# Ethernet_Connector.net
KiCad netlist of a schematic drawn in Altium Designer
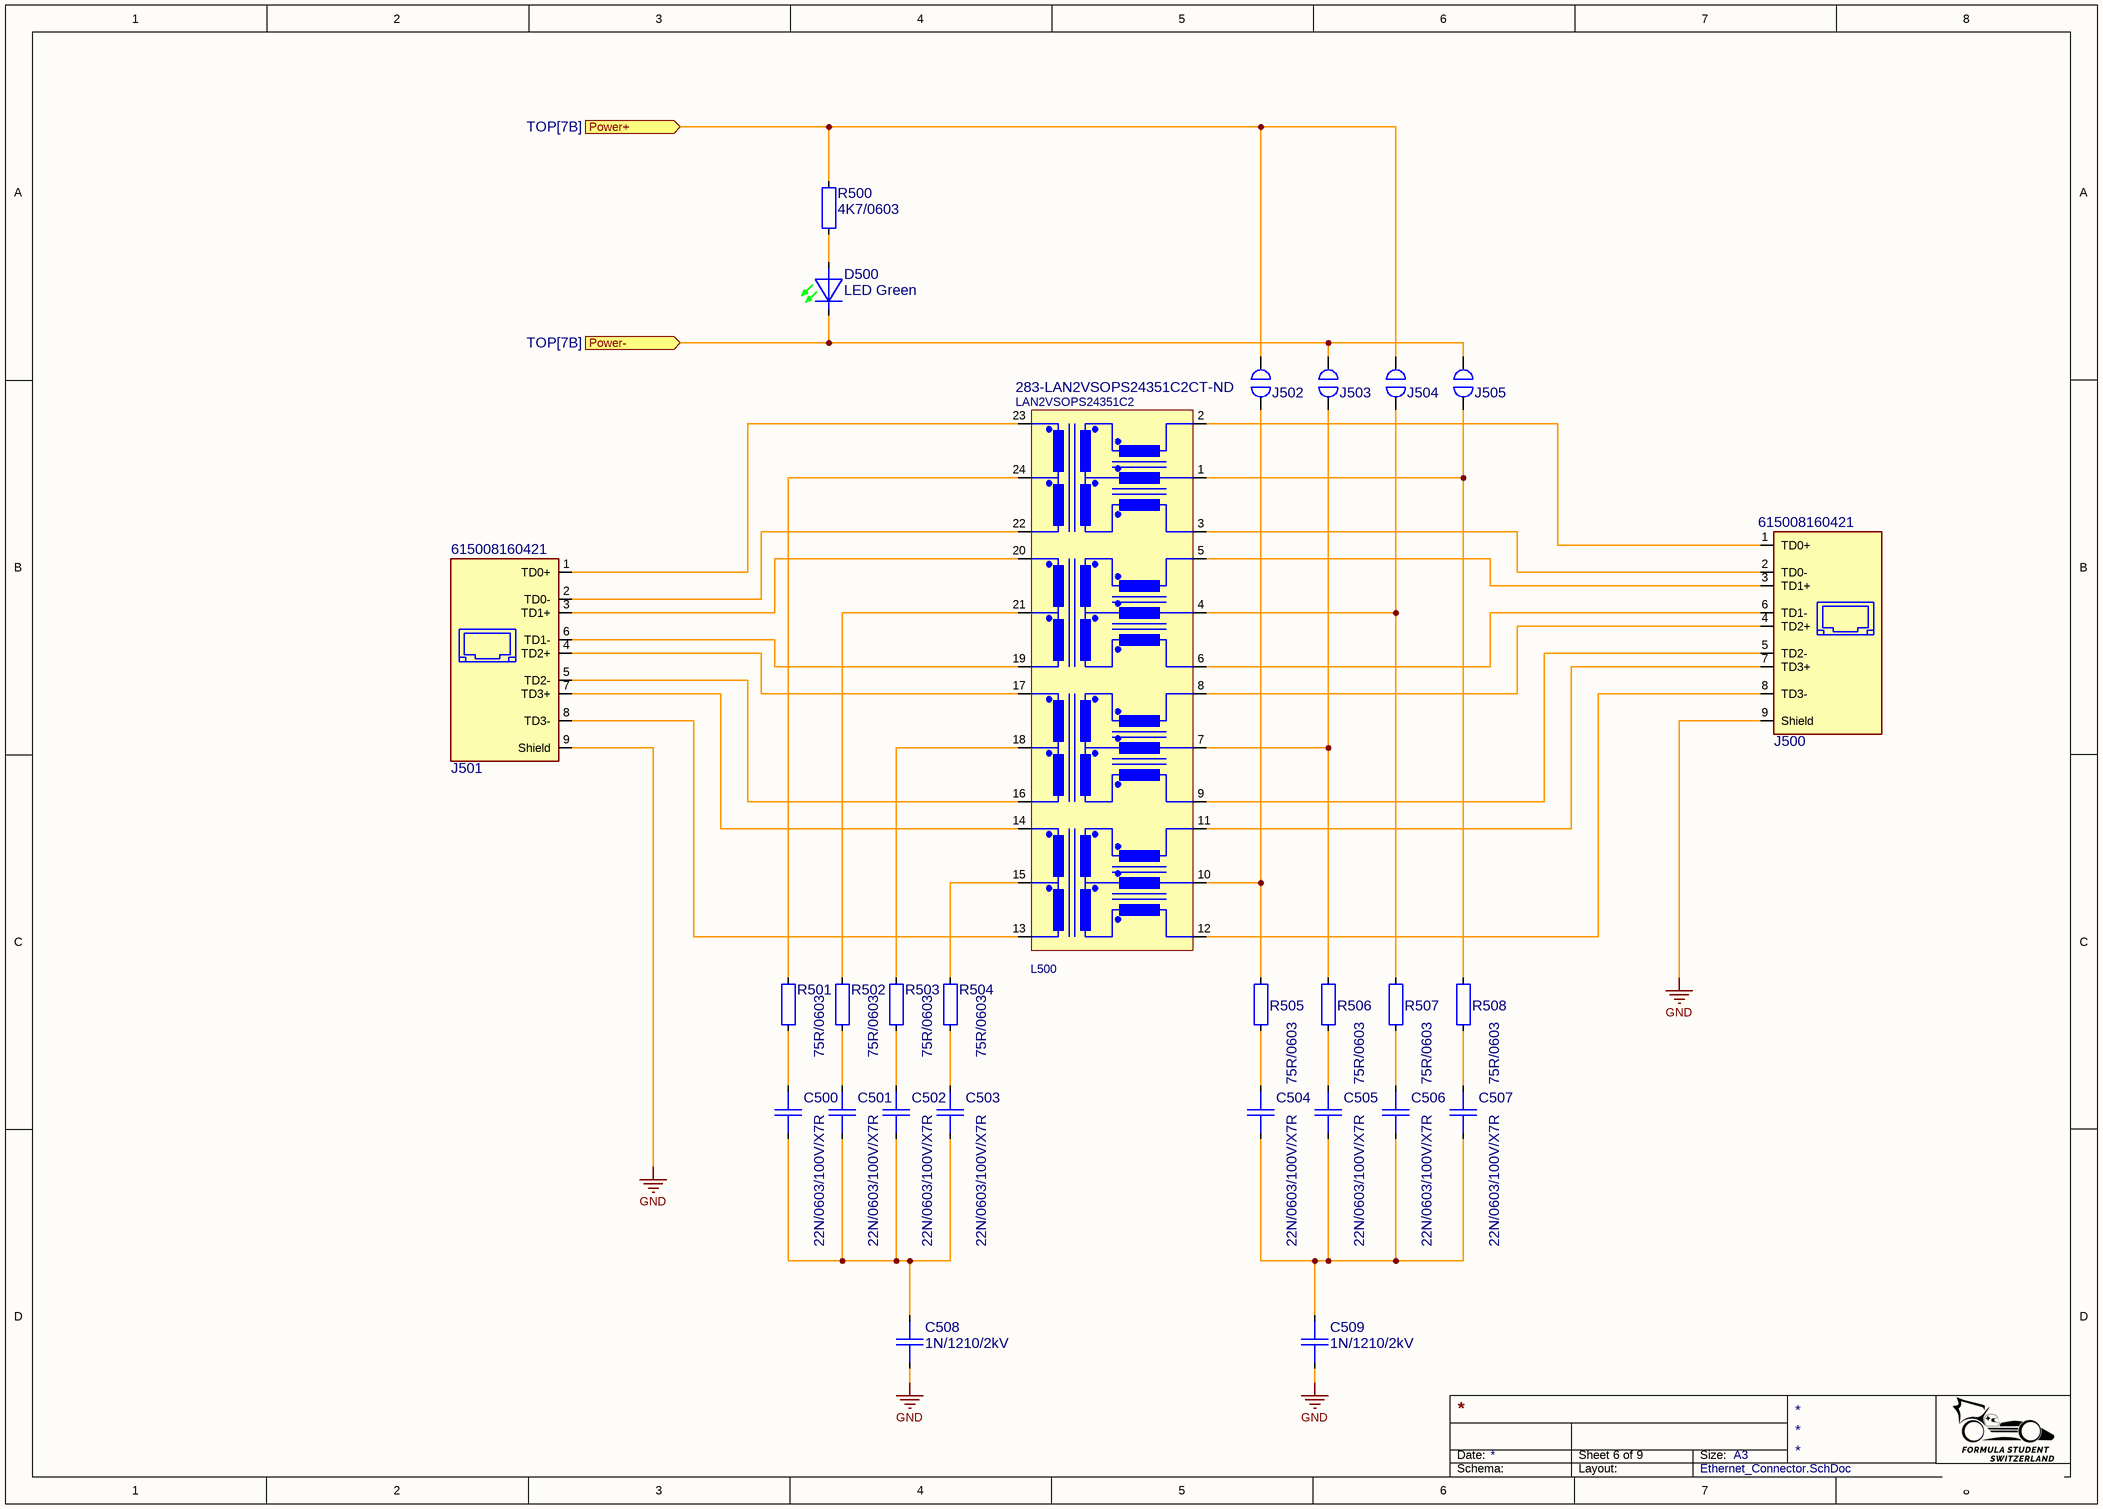
[diagram p0: Ethernet_Connector.SchDoc]

(export (version "E")
  (design (tool "Eeschema 10.0.6"))
  (components
    (comp (ref "C500")
      (value "22N/0603/100V/X7R")
      (footprint "CAP0603_X7R")
      (description "CAP SM 0603 22nF 100V X7R")
      (fields (field (name "MANUFACTURER") "GENERIC"))
      (libsource (lib "daniw_altium_lib") (part "C"))
    )
    (comp (ref "C501")
      (value "22N/0603/100V/X7R")
      (footprint "CAP0603_X7R")
      (description "CAP SM 0603 22nF 100V X7R")
      (fields (field (name "MANUFACTURER") "GENERIC"))
      (libsource (lib "daniw_altium_lib") (part "C"))
    )
    (comp (ref "C502")
      (value "22N/0603/100V/X7R")
      (footprint "CAP0603_X7R")
      (description "CAP SM 0603 22nF 100V X7R")
      (fields (field (name "MANUFACTURER") "GENERIC"))
      (libsource (lib "daniw_altium_lib") (part "C"))
    )
    (comp (ref "C503")
      (value "22N/0603/100V/X7R")
      (footprint "CAP0603_X7R")
      (description "CAP SM 0603 22nF 100V X7R")
      (fields (field (name "MANUFACTURER") "GENERIC"))
      (libsource (lib "daniw_altium_lib") (part "C"))
    )
    (comp (ref "C504")
      (value "22N/0603/100V/X7R")
      (footprint "CAP0603_X7R")
      (description "CAP SM 0603 22nF 100V X7R")
      (fields (field (name "MANUFACTURER") "GENERIC"))
      (libsource (lib "daniw_altium_lib") (part "C"))
    )
    (comp (ref "C505")
      (value "22N/0603/100V/X7R")
      (footprint "CAP0603_X7R")
      (description "CAP SM 0603 22nF 100V X7R")
      (fields (field (name "MANUFACTURER") "GENERIC"))
      (libsource (lib "daniw_altium_lib") (part "C"))
    )
    (comp (ref "C506")
      (value "22N/0603/100V/X7R")
      (footprint "CAP0603_X7R")
      (description "CAP SM 0603 22nF 100V X7R")
      (fields (field (name "MANUFACTURER") "GENERIC"))
      (libsource (lib "daniw_altium_lib") (part "C"))
    )
    (comp (ref "C507")
      (value "22N/0603/100V/X7R")
      (footprint "CAP0603_X7R")
      (description "CAP SM 0603 22nF 100V X7R")
      (fields (field (name "MANUFACTURER") "GENERIC"))
      (libsource (lib "daniw_altium_lib") (part "C"))
    )
    (comp (ref "C508")
      (value "1N/1210/2kV")
      (footprint "CAP1210_X7R")
      (description "CAP SM 1210 1nF 2kV")
      (fields (field (name "MANUFACTURER") "GENERIC"))
      (libsource (lib "daniw_altium_lib") (part "C"))
    )
    (comp (ref "C509")
      (value "1N/1210/2kV")
      (footprint "CAP1210_X7R")
      (description "CAP SM 1210 1nF 2kV")
      (fields (field (name "MANUFACTURER") "GENERIC"))
      (libsource (lib "daniw_altium_lib") (part "C"))
    )
    (comp (ref "D500")
      (value "LED Green")
      (footprint "LED0603_GREEN")
      (description "Generic LED Green 0603")
      (fields (field (name "PART NUMBER") "LED Green 0603") (field (name "MANUFACTURER") "GENERIC"))
      (libsource (lib "daniw_altium_lib") (part "LED_GREEN"))
    )
    (comp (ref "J500")
      (value "615008160421")
      (footprint "ETH_615008160421")
      (description "CONN MOD JACK 8P8C VERT SHIELDED")
      (fields (field (name "PART NUMBER") "ETH_THT_Vert_Schielded") (field (name "MANUFACTURER") "GENERIC"))
      (libsource (lib "daniw_altium_lib") (part "RJ-45 ETH W/O LED"))
    )
    (comp (ref "J501")
      (value "615008160421")
      (footprint "ETH_615008160421")
      (description "CONN MOD JACK 8P8C VERT SHIELDED")
      (fields (field (name "PART NUMBER") "ETH_THT_Vert_Schielded") (field (name "MANUFACTURER") "GENERIC"))
      (libsource (lib "") (part "RJ-45 ETH W/O LED_1"))
    )
    (comp (ref "J502")
      (value "Solder Jumper 2pin 0.2mm small")
      (footprint "Solder_Jumper_2pin_0.2mm_small")
      (description "Solder jumper with two pins with a spacing of 0.2mm")
      (fields
        (field (name "PART NUMBER") "Solder_Jumper_2pin_0.2mm_small")
        (field (name "MANUFACTURER") "NONE")
      )
      (libsource (lib "daniw_altium_lib") (part "SolderJumper_2"))
    )
    (comp (ref "J503")
      (value "Solder Jumper 2pin 0.2mm small")
      (footprint "Solder_Jumper_2pin_0.2mm_small")
      (description "Solder jumper with two pins with a spacing of 0.2mm")
      (fields
        (field (name "PART NUMBER") "Solder_Jumper_2pin_0.2mm_small")
        (field (name "MANUFACTURER") "NONE")
      )
      (libsource (lib "daniw_altium_lib") (part "SolderJumper_2"))
    )
    (comp (ref "J504")
      (value "Solder Jumper 2pin 0.2mm small")
      (footprint "Solder_Jumper_2pin_0.2mm_small")
      (description "Solder jumper with two pins with a spacing of 0.2mm")
      (fields
        (field (name "PART NUMBER") "Solder_Jumper_2pin_0.2mm_small")
        (field (name "MANUFACTURER") "NONE")
      )
      (libsource (lib "daniw_altium_lib") (part "SolderJumper_2"))
    )
    (comp (ref "J505")
      (value "Solder Jumper 2pin 0.2mm small")
      (footprint "Solder_Jumper_2pin_0.2mm_small")
      (description "Solder jumper with two pins with a spacing of 0.2mm")
      (fields
        (field (name "PART NUMBER") "Solder_Jumper_2pin_0.2mm_small")
        (field (name "MANUFACTURER") "NONE")
      )
      (libsource (lib "daniw_altium_lib") (part "SolderJumper_2"))
    )
    (comp (ref "L500")
      (value "LAN2VSOPS24351C2")
      (footprint "IND127P1600X620-24")
      (description "350µH LAN 1000 Base-T, Power over Ethernet (PoE) Pulswandler 1CT:1CT Oberflächenmontage")
      (fields
        (field (name "MANUFACTURER") "Eaton")
        (field (name "SUPPLIER PART NUMBER 1") "283-LAN2VSOPS24351C2CT-ND")
      )
      (libsource (lib "daniw_altium_lib") (part "Pulse_4Channel_CT"))
    )
    (comp (ref "R500")
      (value "4K7/0603")
      (footprint "R0603-0.40-WW")
      (description "RES SM 0603 4K7")
      (fields (field (name "MANUFACTURER") "GENERIC"))
      (libsource (lib "daniw_altium_lib") (part "R"))
    )
    (comp (ref "R501")
      (value "75R/0603")
      (footprint "R0603-0.40-WW")
      (description "RES SM 0603 75R")
      (fields (field (name "MANUFACTURER") "GENERIC"))
      (libsource (lib "daniw_altium_lib") (part "R"))
    )
    (comp (ref "R502")
      (value "75R/0603")
      (footprint "R0603-0.40-WW")
      (description "RES SM 0603 75R")
      (fields (field (name "MANUFACTURER") "GENERIC"))
      (libsource (lib "daniw_altium_lib") (part "R"))
    )
    (comp (ref "R503")
      (value "75R/0603")
      (footprint "R0603-0.40-WW")
      (description "RES SM 0603 75R")
      (fields (field (name "MANUFACTURER") "GENERIC"))
      (libsource (lib "daniw_altium_lib") (part "R"))
    )
    (comp (ref "R504")
      (value "75R/0603")
      (footprint "R0603-0.40-WW")
      (description "RES SM 0603 75R")
      (fields (field (name "MANUFACTURER") "GENERIC"))
      (libsource (lib "daniw_altium_lib") (part "R"))
    )
    (comp (ref "R505")
      (value "75R/0603")
      (footprint "R0603-0.40-WW")
      (description "RES SM 0603 75R")
      (fields (field (name "MANUFACTURER") "GENERIC"))
      (libsource (lib "daniw_altium_lib") (part "R"))
    )
    (comp (ref "R506")
      (value "75R/0603")
      (footprint "R0603-0.40-WW")
      (description "RES SM 0603 75R")
      (fields (field (name "MANUFACTURER") "GENERIC"))
      (libsource (lib "daniw_altium_lib") (part "R"))
    )
    (comp (ref "R507")
      (value "75R/0603")
      (footprint "R0603-0.40-WW")
      (description "RES SM 0603 75R")
      (fields (field (name "MANUFACTURER") "GENERIC"))
      (libsource (lib "daniw_altium_lib") (part "R"))
    )
    (comp (ref "R508")
      (value "75R/0603")
      (footprint "R0603-0.40-WW")
      (description "RES SM 0603 75R")
      (fields (field (name "MANUFACTURER") "GENERIC"))
      (libsource (lib "daniw_altium_lib") (part "R"))
    )
  )
  (nets
    (net (code "1") (name "/Power+") (class "Default")
      (node (ref "J502") (pin "1") (pinfunction "1_1") (pintype "passive"))
      (node (ref "J504") (pin "1") (pinfunction "1_1") (pintype "passive"))
      (node (ref "R500") (pin "2") (pinfunction "2_2") (pintype "passive"))
    )
    (net (code "2") (name "/Power-") (class "Default")
      (node (ref "D500") (pin "1") (pinfunction "1_1") (pintype "passive"))
      (node (ref "J503") (pin "1") (pinfunction "1_1") (pintype "passive"))
      (node (ref "J505") (pin "1") (pinfunction "1_1") (pintype "passive"))
    )
    (net (code "3") (name "GND") (class "Default")
      (node (ref "C508") (pin "2") (pinfunction "2_2") (pintype "passive"))
      (node (ref "C509") (pin "2") (pinfunction "2_2") (pintype "passive"))
      (node (ref "J500") (pin "9") (pinfunction "Shield_9") (pintype "passive"))
      (node (ref "J501") (pin "9") (pinfunction "Shield_9") (pintype "passive"))
    )
    (net (code "4") (name "Net-(C500-Pad1)") (class "Default")
      (node (ref "C500") (pin "1") (pinfunction "1_1") (pintype "passive"))
      (node (ref "R501") (pin "2") (pinfunction "2_2") (pintype "passive"))
    )
    (net (code "5") (name "Net-(C500-Pad2)") (class "Default")
      (node (ref "C500") (pin "2") (pinfunction "2_2") (pintype "passive"))
      (node (ref "C501") (pin "2") (pinfunction "2_2") (pintype "passive"))
      (node (ref "C502") (pin "2") (pinfunction "2_2") (pintype "passive"))
      (node (ref "C503") (pin "2") (pinfunction "2_2") (pintype "passive"))
      (node (ref "C508") (pin "1") (pinfunction "1_1") (pintype "passive"))
    )
    (net (code "6") (name "Net-(C501-Pad1)") (class "Default")
      (node (ref "C501") (pin "1") (pinfunction "1_1") (pintype "passive"))
      (node (ref "R502") (pin "2") (pinfunction "2_2") (pintype "passive"))
    )
    (net (code "7") (name "Net-(C502-Pad1)") (class "Default")
      (node (ref "C502") (pin "1") (pinfunction "1_1") (pintype "passive"))
      (node (ref "R503") (pin "2") (pinfunction "2_2") (pintype "passive"))
    )
    (net (code "8") (name "Net-(C503-Pad1)") (class "Default")
      (node (ref "C503") (pin "1") (pinfunction "1_1") (pintype "passive"))
      (node (ref "R504") (pin "2") (pinfunction "2_2") (pintype "passive"))
    )
    (net (code "9") (name "Net-(C504-Pad1)") (class "Default")
      (node (ref "C504") (pin "1") (pinfunction "1_1") (pintype "passive"))
      (node (ref "R505") (pin "2") (pinfunction "2_2") (pintype "passive"))
    )
    (net (code "10") (name "Net-(C504-Pad2)") (class "Default")
      (node (ref "C504") (pin "2") (pinfunction "2_2") (pintype "passive"))
      (node (ref "C505") (pin "2") (pinfunction "2_2") (pintype "passive"))
      (node (ref "C506") (pin "2") (pinfunction "2_2") (pintype "passive"))
      (node (ref "C507") (pin "2") (pinfunction "2_2") (pintype "passive"))
      (node (ref "C509") (pin "1") (pinfunction "1_1") (pintype "passive"))
    )
    (net (code "11") (name "Net-(C505-Pad1)") (class "Default")
      (node (ref "C505") (pin "1") (pinfunction "1_1") (pintype "passive"))
      (node (ref "R506") (pin "2") (pinfunction "2_2") (pintype "passive"))
    )
    (net (code "12") (name "Net-(C506-Pad1)") (class "Default")
      (node (ref "C506") (pin "1") (pinfunction "1_1") (pintype "passive"))
      (node (ref "R507") (pin "2") (pinfunction "2_2") (pintype "passive"))
    )
    (net (code "13") (name "Net-(C507-Pad1)") (class "Default")
      (node (ref "C507") (pin "1") (pinfunction "1_1") (pintype "passive"))
      (node (ref "R508") (pin "2") (pinfunction "2_2") (pintype "passive"))
    )
    (net (code "14") (name "Net-(D500-Pad2)") (class "Default")
      (node (ref "D500") (pin "2") (pinfunction "2_2") (pintype "passive"))
      (node (ref "R500") (pin "1") (pinfunction "1_1") (pintype "passive"))
    )
    (net (code "15") (name "Net-(J500-TD0+)") (class "Default")
      (node (ref "J500") (pin "1") (pinfunction "TD0+_1") (pintype "passive"))
      (node (ref "L500") (pin "2") (pintype "passive"))
    )
    (net (code "16") (name "Net-(J500-TD0-)") (class "Default")
      (node (ref "J500") (pin "2") (pinfunction "TD0-_2") (pintype "passive"))
      (node (ref "L500") (pin "3") (pintype "passive"))
    )
    (net (code "17") (name "Net-(J500-TD1+)") (class "Default")
      (node (ref "J500") (pin "3") (pinfunction "TD1+_3") (pintype "passive"))
      (node (ref "L500") (pin "5") (pintype "passive"))
    )
    (net (code "18") (name "Net-(J500-TD1-)") (class "Default")
      (node (ref "J500") (pin "6") (pinfunction "TD1-_6") (pintype "passive"))
      (node (ref "L500") (pin "6") (pintype "passive"))
    )
    (net (code "19") (name "Net-(J500-TD2+)") (class "Default")
      (node (ref "J500") (pin "4") (pinfunction "TD2+_4") (pintype "passive"))
      (node (ref "L500") (pin "8") (pintype "passive"))
    )
    (net (code "20") (name "Net-(J500-TD2-)") (class "Default")
      (node (ref "J500") (pin "5") (pinfunction "TD2-_5") (pintype "passive"))
      (node (ref "L500") (pin "9") (pintype "passive"))
    )
    (net (code "21") (name "Net-(J500-TD3+)") (class "Default")
      (node (ref "J500") (pin "7") (pinfunction "TD3+_7") (pintype "passive"))
      (node (ref "L500") (pin "11") (pintype "passive"))
    )
    (net (code "22") (name "Net-(J500-TD3-)") (class "Default")
      (node (ref "J500") (pin "8") (pinfunction "TD3-_8") (pintype "passive"))
      (node (ref "L500") (pin "12") (pintype "passive"))
    )
    (net (code "23") (name "Net-(J501-TD0+)") (class "Default")
      (node (ref "J501") (pin "1") (pinfunction "TD0+_1") (pintype "passive"))
      (node (ref "L500") (pin "23") (pintype "passive"))
    )
    (net (code "24") (name "Net-(J501-TD0-)") (class "Default")
      (node (ref "J501") (pin "2") (pinfunction "TD0-_2") (pintype "passive"))
      (node (ref "L500") (pin "22") (pintype "passive"))
    )
    (net (code "25") (name "Net-(J501-TD1+)") (class "Default")
      (node (ref "J501") (pin "3") (pinfunction "TD1+_3") (pintype "passive"))
      (node (ref "L500") (pin "20") (pintype "passive"))
    )
    (net (code "26") (name "Net-(J501-TD1-)") (class "Default")
      (node (ref "J501") (pin "6") (pinfunction "TD1-_6") (pintype "passive"))
      (node (ref "L500") (pin "19") (pintype "passive"))
    )
    (net (code "27") (name "Net-(J501-TD2+)") (class "Default")
      (node (ref "J501") (pin "4") (pinfunction "TD2+_4") (pintype "passive"))
      (node (ref "L500") (pin "17") (pintype "passive"))
    )
    (net (code "28") (name "Net-(J501-TD2-)") (class "Default")
      (node (ref "J501") (pin "5") (pinfunction "TD2-_5") (pintype "passive"))
      (node (ref "L500") (pin "16") (pintype "passive"))
    )
    (net (code "29") (name "Net-(J501-TD3+)") (class "Default")
      (node (ref "J501") (pin "7") (pinfunction "TD3+_7") (pintype "passive"))
      (node (ref "L500") (pin "14") (pintype "passive"))
    )
    (net (code "30") (name "Net-(J501-TD3-)") (class "Default")
      (node (ref "J501") (pin "8") (pinfunction "TD3-_8") (pintype "passive"))
      (node (ref "L500") (pin "13") (pintype "passive"))
    )
    (net (code "31") (name "Net-(J502-Pad2)") (class "Default")
      (node (ref "J502") (pin "2") (pinfunction "2_2") (pintype "passive"))
      (node (ref "L500") (pin "10") (pintype "passive"))
      (node (ref "R505") (pin "1") (pinfunction "1_1") (pintype "passive"))
    )
    (net (code "32") (name "Net-(J503-Pad2)") (class "Default")
      (node (ref "J503") (pin "2") (pinfunction "2_2") (pintype "passive"))
      (node (ref "L500") (pin "7") (pintype "passive"))
      (node (ref "R506") (pin "1") (pinfunction "1_1") (pintype "passive"))
    )
    (net (code "33") (name "Net-(J504-Pad2)") (class "Default")
      (node (ref "J504") (pin "2") (pinfunction "2_2") (pintype "passive"))
      (node (ref "L500") (pin "4") (pintype "passive"))
      (node (ref "R507") (pin "1") (pinfunction "1_1") (pintype "passive"))
    )
    (net (code "34") (name "Net-(J505-Pad2)") (class "Default")
      (node (ref "J505") (pin "2") (pinfunction "2_2") (pintype "passive"))
      (node (ref "L500") (pin "1") (pintype "passive"))
      (node (ref "R508") (pin "1") (pinfunction "1_1") (pintype "passive"))
    )
    (net (code "35") (name "Net-(L500-Pad15)") (class "Default")
      (node (ref "L500") (pin "15") (pintype "passive"))
      (node (ref "R504") (pin "1") (pinfunction "1_1") (pintype "passive"))
    )
    (net (code "36") (name "Net-(L500-Pad18)") (class "Default")
      (node (ref "L500") (pin "18") (pintype "passive"))
      (node (ref "R503") (pin "1") (pinfunction "1_1") (pintype "passive"))
    )
    (net (code "37") (name "Net-(L500-Pad21)") (class "Default")
      (node (ref "L500") (pin "21") (pintype "passive"))
      (node (ref "R502") (pin "1") (pinfunction "1_1") (pintype "passive"))
    )
    (net (code "38") (name "Net-(L500-Pad24)") (class "Default")
      (node (ref "L500") (pin "24") (pintype "passive"))
      (node (ref "R501") (pin "1") (pinfunction "1_1") (pintype "passive"))
    )
  )
)
